# schematic.net
KiCad netlist of a schematic drawn in EasyEDA Pro
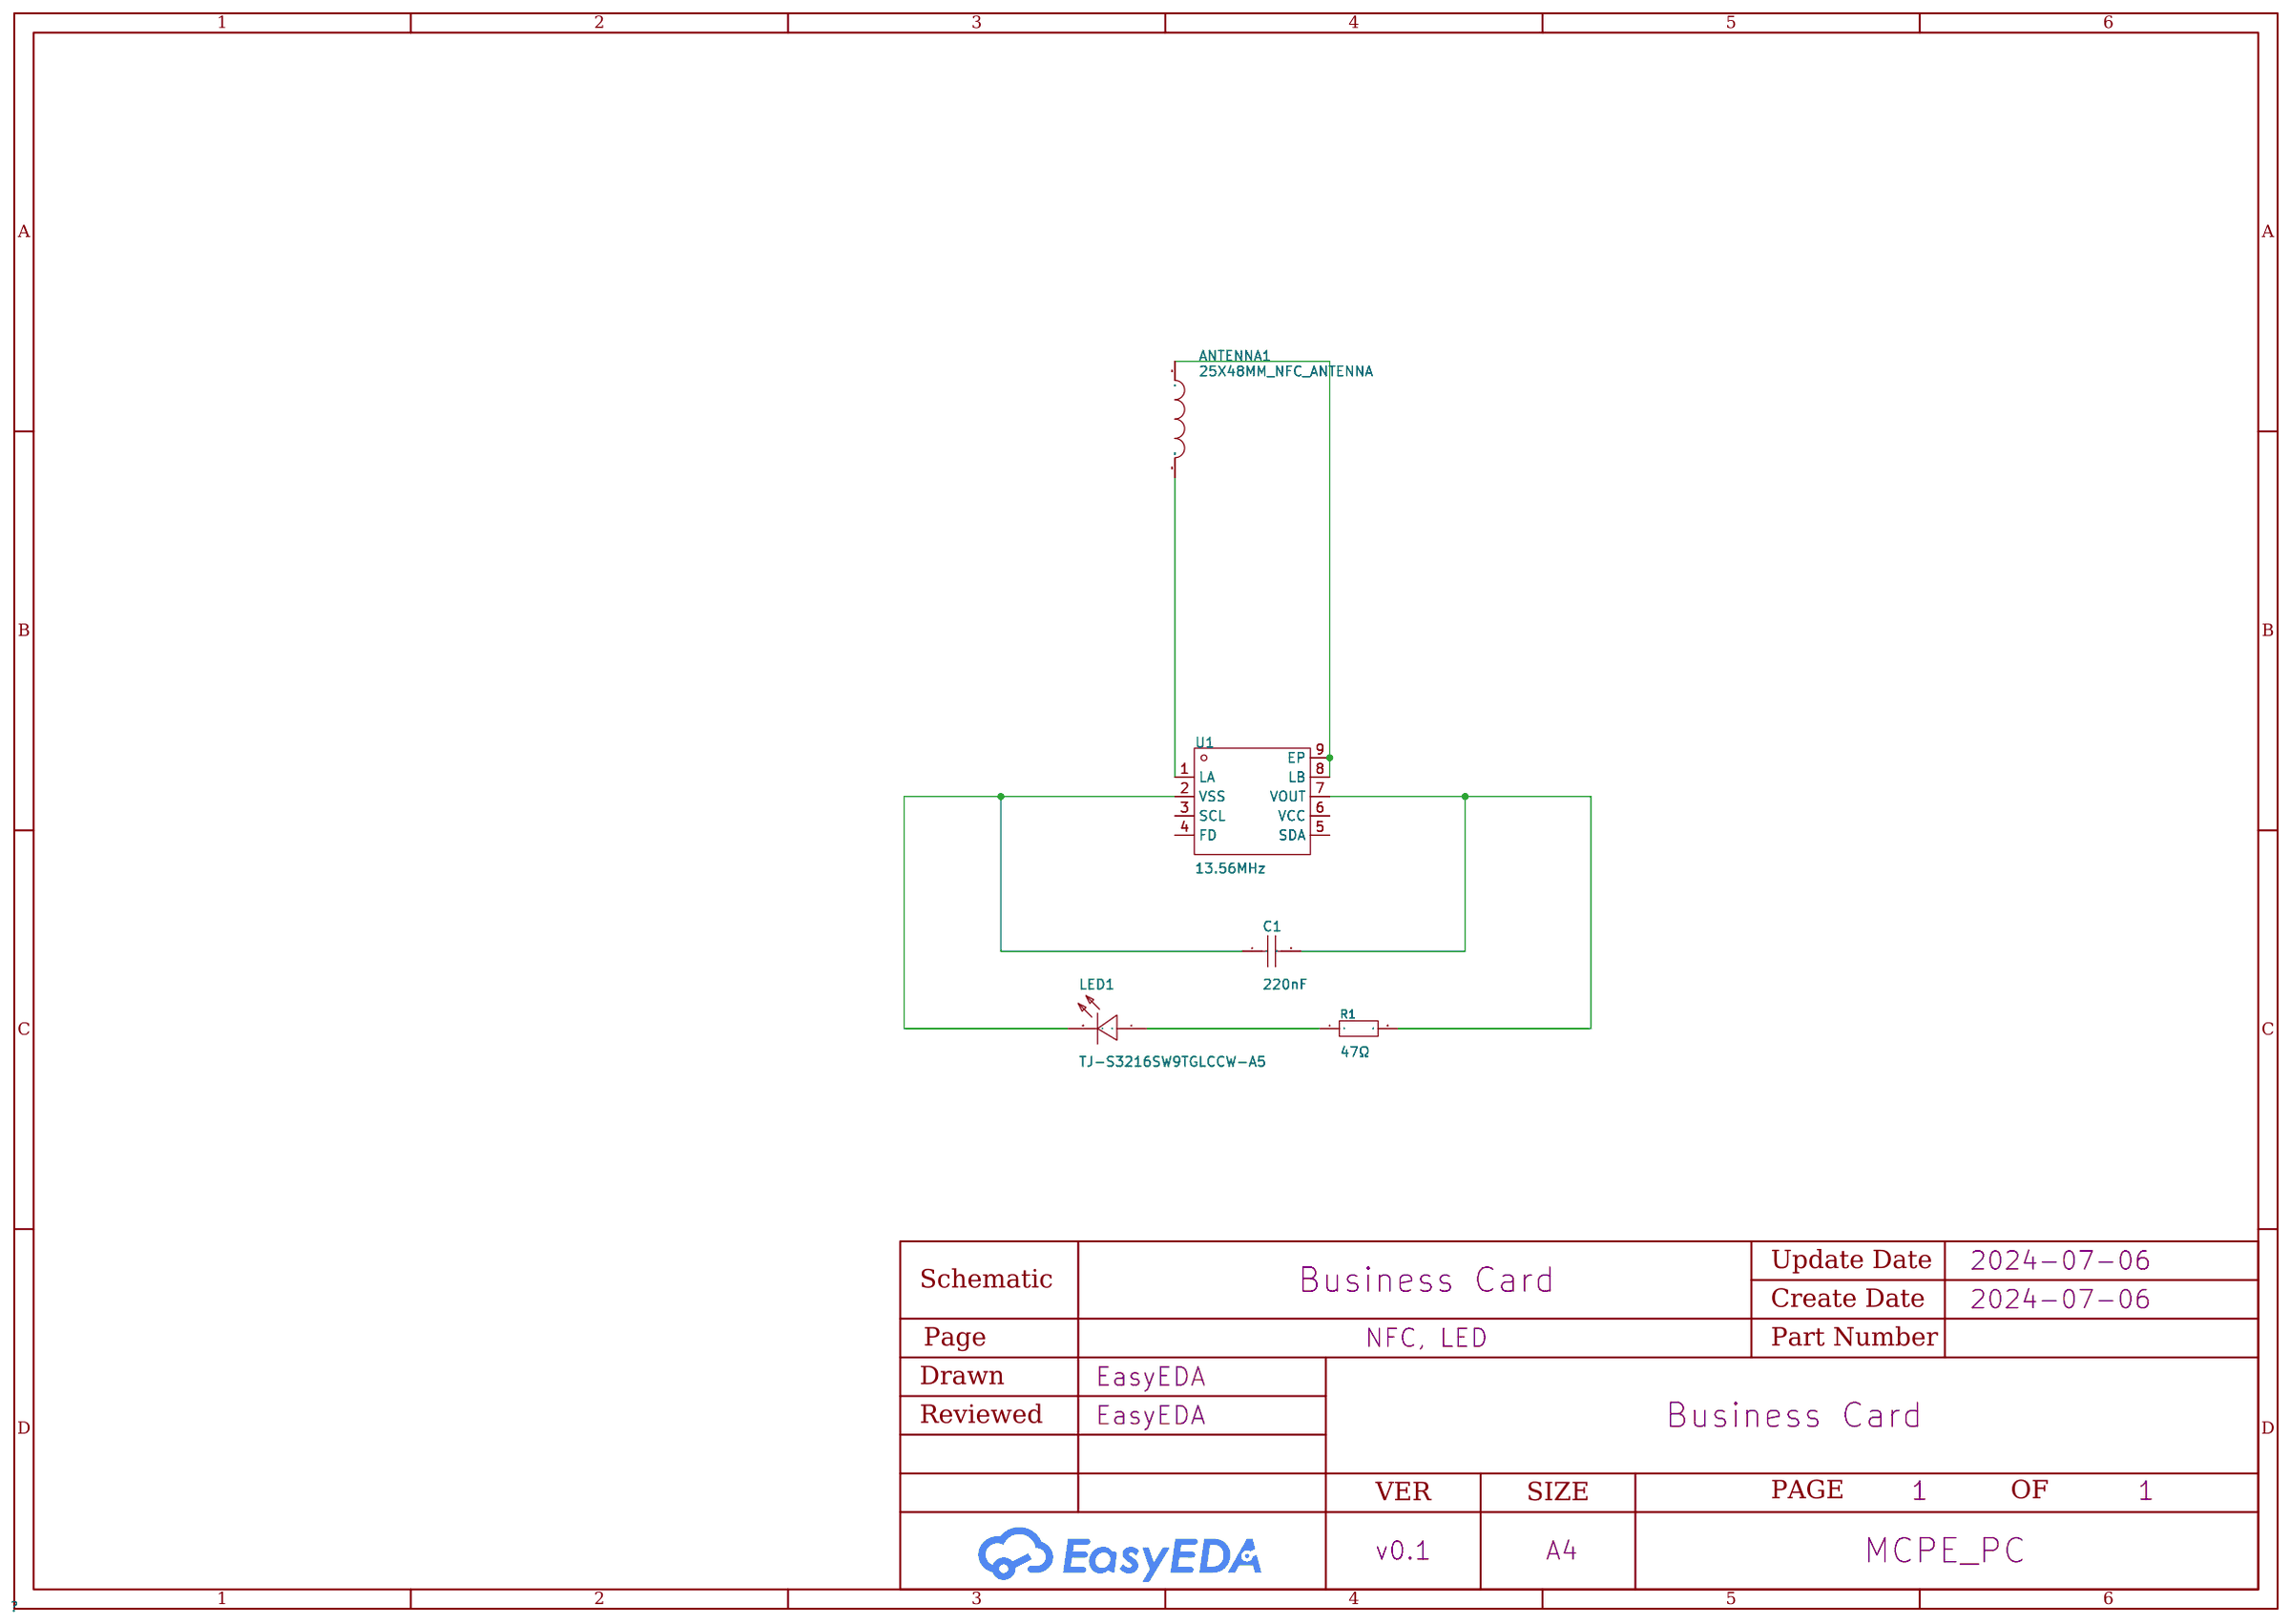
[diagram p0: schematic sheet]

(export (version "E")
  (design (tool "Eeschema 10.0.6"))
  (components
    (comp (ref "ANTENNA1")
      (value "25X48MM_NFC_ANTENNA")
      (libsource (lib "easyedapro") (part "25X48MM_NFC_ANTENNA"))
    )
    (comp (ref "C1")
      (value "220nF")
      (footprint "easyedapro:C0603")
      (fields
        (field (name "Manufacturer Part") "CL10B224KA8NNNC")
        (field (name "Manufacturer") "SAMSUNG(三星)")
      )
      (libsource (lib "easyedapro") (part "CL10B224KA8NNNC"))
    )
    (comp (ref "LED1")
      (value "TJ-S3216SW9TGLCCW-A5")
      (footprint "easyedapro:LED1206-R-RD_WHITE")
      (fields (field (name "Manufacturer") "TOGIALED(统佳)"))
      (libsource (lib "easyedapro") (part "TJ-S3216SW9TGLCCW-A5"))
    )
    (comp (ref "R1")
      (value "47Ω")
      (footprint "easyedapro:R0603")
      (fields
        (field (name "Manufacturer Part") "0603WAF470JT5E")
        (field (name "Manufacturer") "UNI-ROYAL(厚声)")
      )
      (libsource (lib "easyedapro") (part "0603WAF470JT5E"))
    )
    (comp (ref "U1")
      (value "13.56MHz")
      (footprint "easyedapro:XQFN-8_L1.6-W1.6-P0.50-BL")
      (fields (field (name "Manufacturer Part") "NT3H2111W0FHKH") (field (name "Manufacturer") "NXP(恩智浦)"))
      (libsource (lib "easyedapro") (part "NT3H2111W0FHKH"))
    )
  )
  (nets
    (net (code "1") (name "Net-(LED1-A)") (class "Default")
      (node (ref "LED1") (pin "1") (pinfunction "A_1") (pintype "unspecified"))
      (node (ref "R1") (pin "1") (pinfunction "1_1") (pintype "input"))
    )
    (net (code "2") (name "Net-(LED1-K)") (class "Default")
      (node (ref "C1") (pin "1") (pinfunction "1_1") (pintype "input"))
      (node (ref "LED1") (pin "2") (pinfunction "K_2") (pintype "unspecified"))
      (node (ref "U1") (pin "2") (pinfunction "VSS_2") (pintype "unspecified"))
    )
    (net (code "3") (name "Net-(U1-EP)") (class "Default")
      (node (ref "ANTENNA1") (pin "P$1") (pinfunction "P$1_P$1") (pintype "bidirectional"))
      (node (ref "U1") (pin "8") (pinfunction "LB_8") (pintype "unspecified"))
      (node (ref "U1") (pin "9") (pinfunction "EP_9") (pintype "unspecified"))
    )
    (net (code "4") (name "Net-(U1-LA)") (class "Default")
      (node (ref "ANTENNA1") (pin "P$2") (pinfunction "P$2_P$2") (pintype "bidirectional"))
      (node (ref "U1") (pin "1") (pinfunction "LA_1") (pintype "unspecified"))
    )
    (net (code "5") (name "Net-(U1-VOUT)") (class "Default")
      (node (ref "C1") (pin "2") (pinfunction "2_2") (pintype "input"))
      (node (ref "R1") (pin "2") (pinfunction "2_2") (pintype "input"))
      (node (ref "U1") (pin "7") (pinfunction "VOUT_7") (pintype "unspecified"))
    )
    (net (code "6") (name "unconnected-(U1-FD-Pad4)") (class "Default")
      (node (ref "U1") (pin "4") (pinfunction "FD_4") (pintype "unspecified"))
    )
    (net (code "7") (name "unconnected-(U1-SCL-Pad3)") (class "Default")
      (node (ref "U1") (pin "3") (pinfunction "SCL_3") (pintype "unspecified"))
    )
    (net (code "8") (name "unconnected-(U1-SDA-Pad5)") (class "Default")
      (node (ref "U1") (pin "5") (pinfunction "SDA_5") (pintype "unspecified"))
    )
    (net (code "9") (name "unconnected-(U1-VCC-Pad6)") (class "Default")
      (node (ref "U1") (pin "6") (pinfunction "VCC_6") (pintype "unspecified"))
    )
  )
)
